# hhv-dcdarknet-varient-3.net
KiCad netlist of a schematic drawn in EAGLE
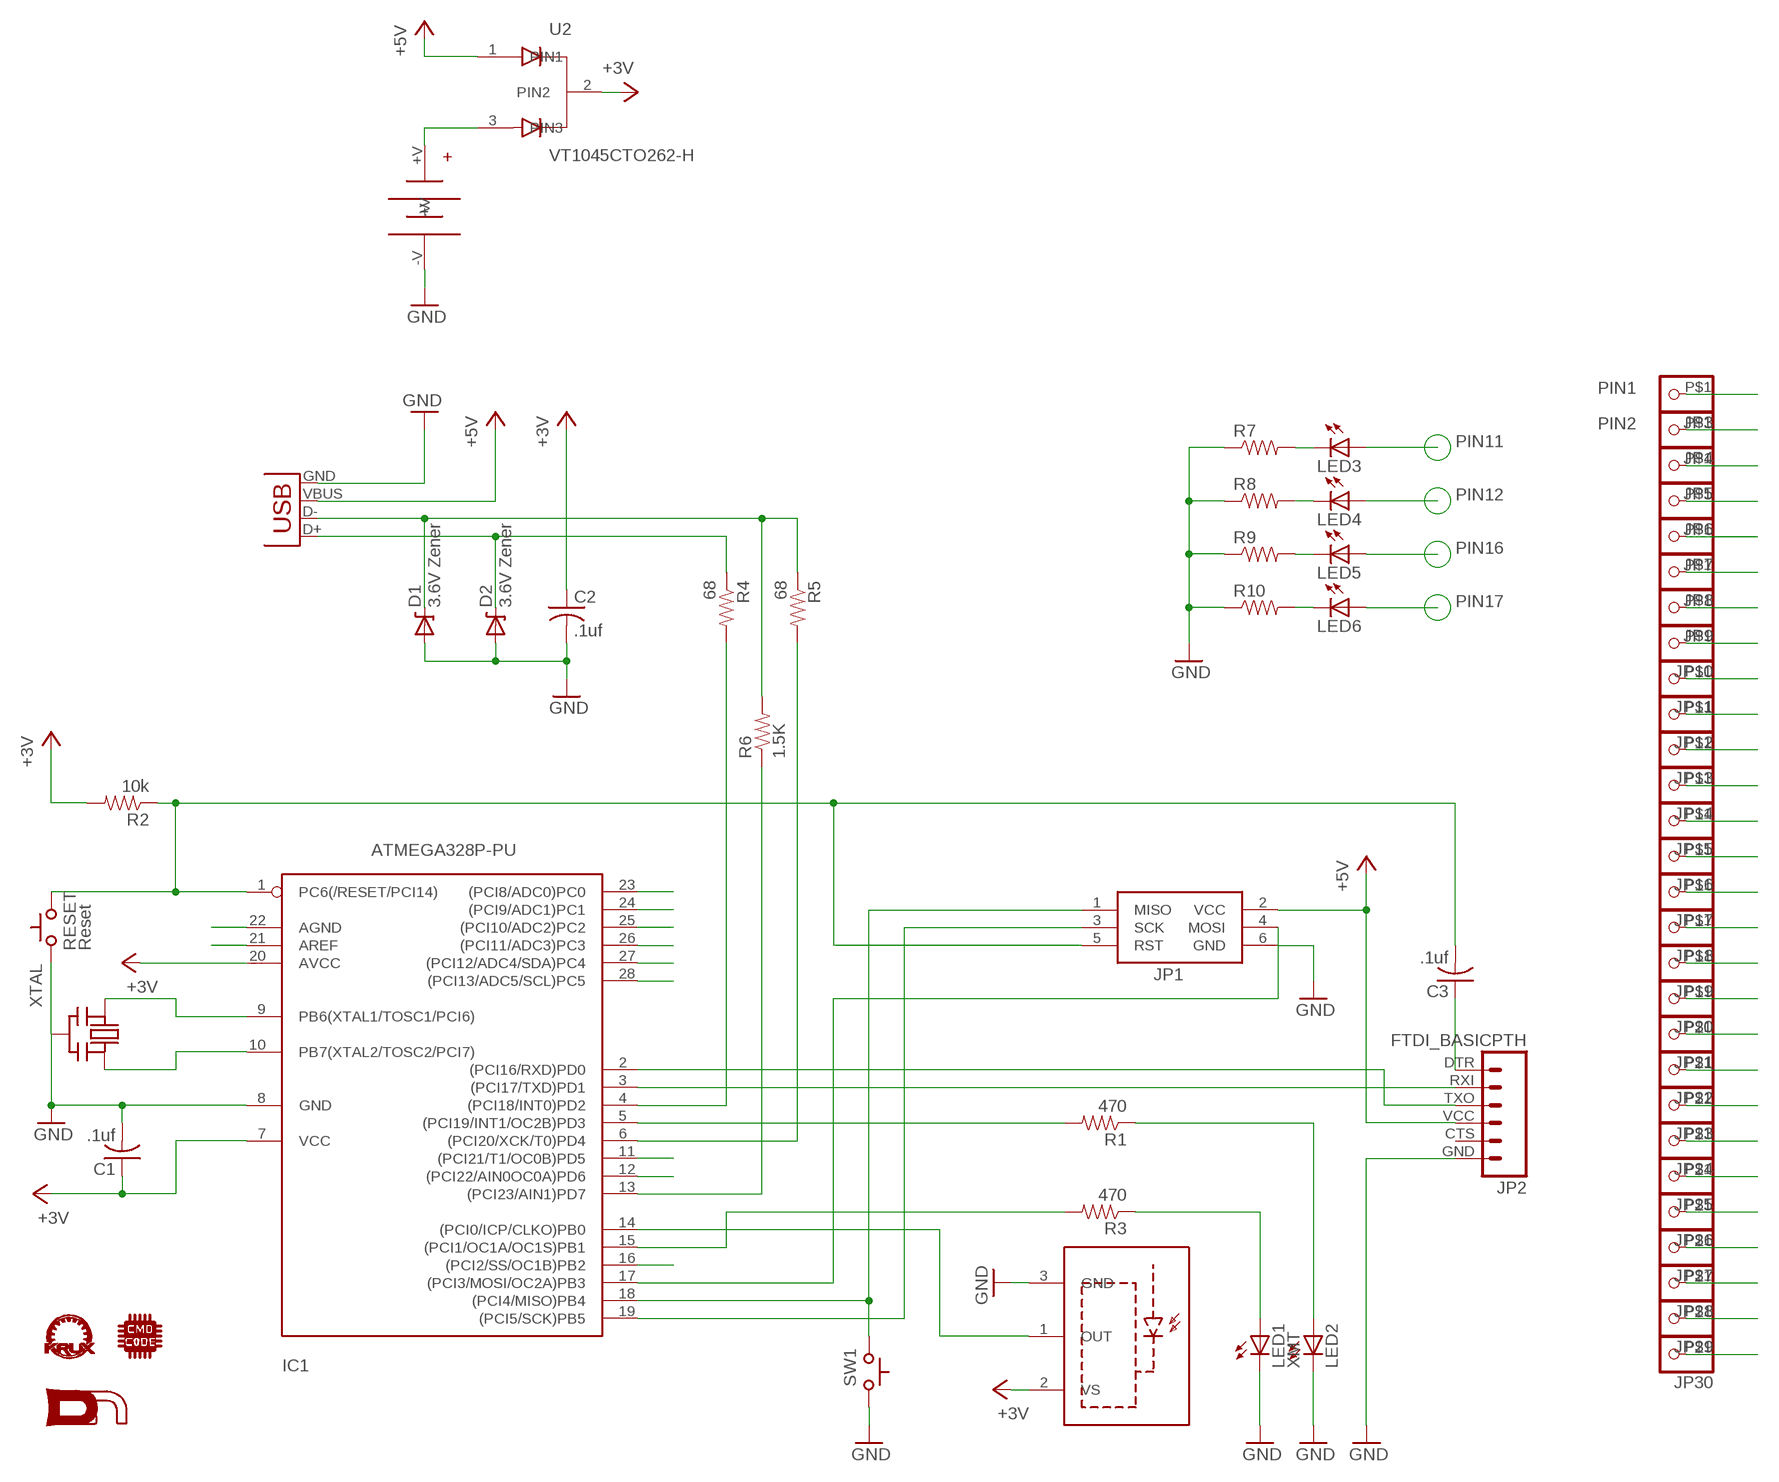
[diagram p0: schematic, sheet 1]

(export (version "E")
  (design (tool "Eeschema 10.0.6"))
  (components
    (comp (ref "C1")
      (value ".1uf")
      (footprint "eagle-import:C025-030X050")
      (libsource (lib "eagle-import") (part "C-US025-030X050"))
    )
    (comp (ref "C2")
      (value ".1uf")
      (footprint "eagle-import:C025-030X050")
      (libsource (lib "eagle-import") (part "C-US025-030X050"))
    )
    (comp (ref "C3")
      (value ".1uf")
      (footprint "eagle-import:C025-030X050")
      (libsource (lib "eagle-import") (part "C-US025-030X050"))
    )
    (comp (ref "D1")
      (value "3.6V Zener")
      (footprint "eagle-import:DIODE-ZENER")
      (libsource (lib "eagle-import") (part "DIODE-ZENERPTH"))
    )
    (comp (ref "D2")
      (value "3.6V Zener")
      (footprint "eagle-import:DIODE-ZENER")
      (libsource (lib "eagle-import") (part "DIODE-ZENERPTH"))
    )
    (comp (ref "IC1")
      (value "ATMEGA328P-PU")
      (footprint "eagle-import:DIL28-3")
      (libsource (lib "eagle-import") (part "ATMEGA168PV-10"))
    )
    (comp (ref "JP1")
      (value "JP1")
      (footprint "eagle-import:AVRISP")
      (libsource (lib "eagle-import") (part "AVRISP-6"))
    )
    (comp (ref "JP2")
      (value "FTDI_BASICPTH")
      (footprint "eagle-import:FTDI_BASIC")
      (libsource (lib "eagle-import") (part "FTDI_BASICPTH"))
    )
    (comp (ref "JP3")
      (value "PINHD-1X11X1_SQUARE")
      (footprint "eagle-import:1X1-SMALL_CUT")
      (libsource (lib "eagle-import") (part "PINHD-1X11X1_SQUARE"))
    )
    (comp (ref "JP4")
      (value "PINHD-1X11X1_SQUARE")
      (footprint "eagle-import:1X1-SMALL_CUT")
      (libsource (lib "eagle-import") (part "PINHD-1X11X1_SQUARE"))
    )
    (comp (ref "JP5")
      (value "PINHD-1X11X1_SQUARE")
      (footprint "eagle-import:1X1-SMALL_CUT")
      (libsource (lib "eagle-import") (part "PINHD-1X11X1_SQUARE"))
    )
    (comp (ref "JP6")
      (value "PINHD-1X11X1_SQUARE")
      (footprint "eagle-import:1X1-SMALL_CUT")
      (libsource (lib "eagle-import") (part "PINHD-1X11X1_SQUARE"))
    )
    (comp (ref "JP7")
      (value "PINHD-1X11X1_SQUARE")
      (footprint "eagle-import:1X1-SMALL_CUT")
      (libsource (lib "eagle-import") (part "PINHD-1X11X1_SQUARE"))
    )
    (comp (ref "JP8")
      (value "PINHD-1X11X1_SQUARE")
      (footprint "eagle-import:1X1-SMALL_CUT")
      (libsource (lib "eagle-import") (part "PINHD-1X11X1_SQUARE"))
    )
    (comp (ref "JP9")
      (value "PINHD-1X11X1_SQUARE")
      (footprint "eagle-import:1X1-SMALL_CUT")
      (libsource (lib "eagle-import") (part "PINHD-1X11X1_SQUARE"))
    )
    (comp (ref "JP10")
      (value "PINHD-1X11X1_SQUARE")
      (footprint "eagle-import:1X1-SMALL_CUT")
      (libsource (lib "eagle-import") (part "PINHD-1X11X1_SQUARE"))
    )
    (comp (ref "JP11")
      (value "PINHD-1X11X1_SQUARE")
      (footprint "eagle-import:1X1-SMALL_CUT")
      (libsource (lib "eagle-import") (part "PINHD-1X11X1_SQUARE"))
    )
    (comp (ref "JP12")
      (value "PINHD-1X11X1_SQUARE")
      (footprint "eagle-import:1X1-SMALL_CUT")
      (libsource (lib "eagle-import") (part "PINHD-1X11X1_SQUARE"))
    )
    (comp (ref "JP13")
      (value "PINHD-1X11X1_SQUARE")
      (footprint "eagle-import:1X1-SMALL_CUT")
      (libsource (lib "eagle-import") (part "PINHD-1X11X1_SQUARE"))
    )
    (comp (ref "JP14")
      (value "PINHD-1X11X1_SQUARE")
      (footprint "eagle-import:1X1-SMALL_CUT")
      (libsource (lib "eagle-import") (part "PINHD-1X11X1_SQUARE"))
    )
    (comp (ref "JP15")
      (value "PINHD-1X11X1_SQUARE")
      (footprint "eagle-import:1X1-SMALL_CUT")
      (libsource (lib "eagle-import") (part "PINHD-1X11X1_SQUARE"))
    )
    (comp (ref "JP16")
      (value "PINHD-1X11X1_SQUARE")
      (footprint "eagle-import:1X1-SMALL_CUT")
      (libsource (lib "eagle-import") (part "PINHD-1X11X1_SQUARE"))
    )
    (comp (ref "JP17")
      (value "PINHD-1X11X1_SQUARE")
      (footprint "eagle-import:1X1-SMALL_CUT")
      (libsource (lib "eagle-import") (part "PINHD-1X11X1_SQUARE"))
    )
    (comp (ref "JP18")
      (value "PINHD-1X11X1_SQUARE")
      (footprint "eagle-import:1X1-SMALL_CUT")
      (libsource (lib "eagle-import") (part "PINHD-1X11X1_SQUARE"))
    )
    (comp (ref "JP19")
      (value "PINHD-1X11X1_SQUARE")
      (footprint "eagle-import:1X1-SMALL_CUT")
      (libsource (lib "eagle-import") (part "PINHD-1X11X1_SQUARE"))
    )
    (comp (ref "JP20")
      (value "PINHD-1X11X1_SQUARE")
      (footprint "eagle-import:1X1-SMALL_CUT")
      (libsource (lib "eagle-import") (part "PINHD-1X11X1_SQUARE"))
    )
    (comp (ref "JP21")
      (value "PINHD-1X11X1_SQUARE")
      (footprint "eagle-import:1X1-SMALL_CUT")
      (libsource (lib "eagle-import") (part "PINHD-1X11X1_SQUARE"))
    )
    (comp (ref "JP22")
      (value "PINHD-1X11X1_SQUARE")
      (footprint "eagle-import:1X1-SMALL_CUT")
      (libsource (lib "eagle-import") (part "PINHD-1X11X1_SQUARE"))
    )
    (comp (ref "JP23")
      (value "PINHD-1X11X1_SQUARE")
      (footprint "eagle-import:1X1-SMALL_CUT")
      (libsource (lib "eagle-import") (part "PINHD-1X11X1_SQUARE"))
    )
    (comp (ref "JP24")
      (value "PINHD-1X11X1_SQUARE")
      (footprint "eagle-import:1X1-SMALL_CUT")
      (libsource (lib "eagle-import") (part "PINHD-1X11X1_SQUARE"))
    )
    (comp (ref "JP25")
      (value "PINHD-1X11X1_SQUARE")
      (footprint "eagle-import:1X1-SMALL_CUT")
      (libsource (lib "eagle-import") (part "PINHD-1X11X1_SQUARE"))
    )
    (comp (ref "JP26")
      (value "PINHD-1X11X1_SQUARE")
      (footprint "eagle-import:1X1-SMALL_CUT")
      (libsource (lib "eagle-import") (part "PINHD-1X11X1_SQUARE"))
    )
    (comp (ref "JP27")
      (value "PINHD-1X11X1_SQUARE")
      (footprint "eagle-import:1X1-SMALL_CUT")
      (libsource (lib "eagle-import") (part "PINHD-1X11X1_SQUARE"))
    )
    (comp (ref "JP28")
      (value "PINHD-1X11X1-SMALL")
      (footprint "eagle-import:1X1-SMALL")
      (libsource (lib "eagle-import") (part "PINHD-1X11X1-SMALL"))
    )
    (comp (ref "JP29")
      (value "PINHD-1X11X1-SMALL")
      (footprint "eagle-import:1X1-SMALL")
      (libsource (lib "eagle-import") (part "PINHD-1X11X1-SMALL"))
    )
    (comp (ref "JP30")
      (value "PINHD-1X11X1-SMALL")
      (footprint "eagle-import:1X1-SMALL")
      (libsource (lib "eagle-import") (part "PINHD-1X11X1-SMALL"))
    )
    (comp (ref "LED1")
      (value "XMT")
      (footprint "eagle-import:LED5MM-FLAT")
      (libsource (lib "eagle-import") (part "LED5MM-FLAT"))
    )
    (comp (ref "LED2")
      (value "LED5MM-FLAT")
      (footprint "eagle-import:LED5MM-FLAT")
      (libsource (lib "eagle-import") (part "LED5MM-FLAT"))
    )
    (comp (ref "LED3")
      (value "LED1206")
      (footprint "eagle-import:LED-1206")
      (libsource (lib "eagle-import") (part "SparkFun_LED1206"))
    )
    (comp (ref "LED4")
      (value "LED1206")
      (footprint "eagle-import:LED-1206")
      (libsource (lib "eagle-import") (part "SparkFun_LED1206"))
    )
    (comp (ref "LED5")
      (value "LED1206")
      (footprint "eagle-import:LED-1206")
      (libsource (lib "eagle-import") (part "SparkFun_LED1206"))
    )
    (comp (ref "LED6")
      (value "LED1206")
      (footprint "eagle-import:LED-1206")
      (libsource (lib "eagle-import") (part "SparkFun_LED1206"))
    )
    (comp (ref "R1")
      (value "470")
      (footprint "eagle-import:AXIAL-0.3")
      (libsource (lib "eagle-import") (part "RESISTORAXIAL-0.3"))
    )
    (comp (ref "R2")
      (value "10k")
      (footprint "eagle-import:AXIAL-0.3")
      (libsource (lib "eagle-import") (part "RESISTORAXIAL-0.3"))
    )
    (comp (ref "R3")
      (value "470")
      (footprint "eagle-import:AXIAL-0.3")
      (libsource (lib "eagle-import") (part "RESISTORAXIAL-0.3"))
    )
    (comp (ref "R4")
      (value "68")
      (footprint "eagle-import:AXIAL-0.3")
      (libsource (lib "eagle-import") (part "RESISTORAXIAL-0.3"))
    )
    (comp (ref "R5")
      (value "68")
      (footprint "eagle-import:AXIAL-0.3")
      (libsource (lib "eagle-import") (part "RESISTORAXIAL-0.3"))
    )
    (comp (ref "R6")
      (value "1.5K")
      (footprint "eagle-import:AXIAL-0.3")
      (libsource (lib "eagle-import") (part "RESISTORAXIAL-0.3"))
    )
    (comp (ref "R7")
      (value "RESISTOR1206")
      (footprint "eagle-import:1206")
      (libsource (lib "eagle-import") (part "SparkFun_RESISTOR1206"))
    )
    (comp (ref "R8")
      (value "RESISTOR1206")
      (footprint "eagle-import:1206")
      (libsource (lib "eagle-import") (part "SparkFun_RESISTOR1206"))
    )
    (comp (ref "R9")
      (value "RESISTOR1206")
      (footprint "eagle-import:1206")
      (libsource (lib "eagle-import") (part "SparkFun_RESISTOR1206"))
    )
    (comp (ref "R10")
      (value "RESISTOR1206")
      (footprint "eagle-import:1206")
      (libsource (lib "eagle-import") (part "SparkFun_RESISTOR1206"))
    )
    (comp (ref "RESET")
      (value "Reset")
      (footprint "eagle-import:TACTILE-2PIN")
      (libsource (lib "eagle-import") (part "SWITCH_TACTILETACTILE-2PIN"))
    )
    (comp (ref "SW1")
      (value "SWITCH_TACTILETACTILE-2PIN")
      (footprint "eagle-import:TACTILE-2PIN")
      (libsource (lib "eagle-import") (part "SWITCH_TACTILETACTILE-2PIN"))
    )
    (comp (ref "U$1")
      (value "DN_LOGO")
      (footprint "eagle-import:DN_LOGO")
      (libsource (lib "eagle-import") (part "DN_LOGO"))
    )
    (comp (ref "U$2")
      (value "CMDC0DE_LOGO")
      (footprint "eagle-import:CMDC0DE")
      (libsource (lib "eagle-import") (part "CMDC0DE_LOGO"))
    )
    (comp (ref "U$3")
      (value "KRUX_LOGO")
      (footprint "eagle-import:KRUX_LOGO")
      (libsource (lib "eagle-import") (part "KRUX_LOGO"))
    )
    (comp (ref "U$5")
      (value "12BH423-GR3-CELL_NOBORDER")
      (footprint "eagle-import:3-AAA-CELL_NOBORDER")
      (libsource (lib "eagle-import") (part "12BH423-GR3-CELL_NOBORDER"))
    )
    (comp (ref "U1")
      (value "RCV")
      (footprint "eagle-import:IR-MODULE")
      (libsource (lib "eagle-import") (part "SOP22"))
    )
    (comp (ref "U2")
      (value "VT1045CTO262-H")
      (footprint "eagle-import:TO262-H")
      (libsource (lib "eagle-import") (part "VT1045CTO262-H"))
    )
    (comp (ref "X2")
      (value "USB")
      (footprint "eagle-import:USB-B-PTH")
      (libsource (lib "eagle-import") (part "USBPTH"))
    )
    (comp (ref "XTAL")
      (value "CERMOSCILL-THM")
      (footprint "eagle-import:CERM_OSC")
      (libsource (lib "eagle-import") (part "CERMOSCILL-THM"))
    )
  )
  (nets
    (net (code "1") (name "+3V") (class "Default")
      (node (ref "C1") (pin "1") (pinfunction "1_1") (pintype "passive"))
      (node (ref "C2") (pin "1") (pinfunction "1_1") (pintype "passive"))
      (node (ref "IC1") (pin "20") (pinfunction "AVCC_20") (pintype "bidirectional"))
      (node (ref "IC1") (pin "7") (pinfunction "VCC_7") (pintype "bidirectional"))
      (node (ref "JP22") (pin "P$1") (pinfunction "1_P$1") (pintype "passive"))
      (node (ref "JP9") (pin "P$1") (pinfunction "1_P$1") (pintype "passive"))
      (node (ref "R2") (pin "P$2") (pinfunction "2_P$2") (pintype "passive"))
      (node (ref "U1") (pin "2") (pinfunction "VS_2") (pintype "bidirectional"))
      (node (ref "U2") (pin "2") (pinfunction "PIN2_2") (pintype "bidirectional"))
    )
    (net (code "2") (name "+5V") (class "Default")
      (node (ref "JP1") (pin "2") (pinfunction "VCC_2") (pintype "power_in"))
      (node (ref "JP2") (pin "VCC") (pinfunction "4_VCC") (pintype "passive"))
      (node (ref "U2") (pin "1") (pinfunction "PIN1_1") (pintype "bidirectional"))
      (node (ref "X2") (pin "VBUS") (pinfunction "VBUS_VBUS") (pintype "bidirectional"))
    )
    (net (code "3") (name "/PIN1") (class "Default")
      (node (ref "C3") (pin "2") (pinfunction "2_2") (pintype "passive"))
      (node (ref "IC1") (pin "1") (pinfunction "PC6(/RESET/PCI14)_1") (pintype "bidirectional"))
      (node (ref "JP1") (pin "5") (pinfunction "RST_5") (pintype "output"))
      (node (ref "JP3") (pin "P$1") (pinfunction "1_P$1") (pintype "passive"))
      (node (ref "R2") (pin "P$1") (pinfunction "1_P$1") (pintype "passive"))
      (node (ref "RESET") (pin "P$1") (pinfunction "A_P$1") (pintype "passive"))
    )
    (net (code "4") (name "/PIN2") (class "Default")
      (node (ref "IC1") (pin "2") (pinfunction "(PCI16/RXD)PD0_2") (pintype "bidirectional"))
      (node (ref "JP2") (pin "TXO") (pinfunction "3_TXO") (pintype "passive"))
      (node (ref "JP4") (pin "P$1") (pinfunction "1_P$1") (pintype "passive"))
    )
    (net (code "5") (name "/PIN3") (class "Default")
      (node (ref "IC1") (pin "3") (pinfunction "(PCI17/TXD)PD1_3") (pintype "bidirectional"))
      (node (ref "JP2") (pin "RXI") (pinfunction "2_RXI") (pintype "passive"))
      (node (ref "JP5") (pin "P$1") (pinfunction "1_P$1") (pintype "passive"))
    )
    (net (code "6") (name "/PIN4") (class "Default")
      (node (ref "IC1") (pin "4") (pinfunction "(PCI18/INT0)PD2_4") (pintype "bidirectional"))
      (node (ref "JP6") (pin "P$1") (pinfunction "1_P$1") (pintype "passive"))
      (node (ref "R4") (pin "P$2") (pinfunction "2_P$2") (pintype "passive"))
    )
    (net (code "7") (name "/PIN5") (class "Default")
      (node (ref "IC1") (pin "5") (pinfunction "(PCI19/INT1/OC2B)PD3_5") (pintype "bidirectional"))
      (node (ref "JP7") (pin "P$1") (pinfunction "1_P$1") (pintype "passive"))
      (node (ref "R1") (pin "P$2") (pinfunction "2_P$2") (pintype "passive"))
    )
    (net (code "8") (name "/PIN6") (class "Default")
      (node (ref "IC1") (pin "6") (pinfunction "(PCI20/XCK/T0)PD4_6") (pintype "bidirectional"))
      (node (ref "JP8") (pin "P$1") (pinfunction "1_P$1") (pintype "passive"))
      (node (ref "R5") (pin "P$2") (pinfunction "2_P$2") (pintype "passive"))
    )
    (net (code "9") (name "/PIN9") (class "Default")
      (node (ref "IC1") (pin "9") (pinfunction "PB6(XTAL1/TOSC1/PCI6)_9") (pintype "bidirectional"))
      (node (ref "JP11") (pin "P$1") (pinfunction "1_P$1") (pintype "passive"))
      (node (ref "XTAL") (pin "P$1") (pinfunction "IN_P$1") (pintype "bidirectional"))
    )
    (net (code "10") (name "/PIN10") (class "Default")
      (node (ref "IC1") (pin "10") (pinfunction "PB7(XTAL2/TOSC2/PCI7)_10") (pintype "bidirectional"))
      (node (ref "JP12") (pin "P$1") (pinfunction "1_P$1") (pintype "passive"))
      (node (ref "XTAL") (pin "P$3") (pinfunction "OUT_P$3") (pintype "bidirectional"))
    )
    (net (code "11") (name "/PIN11") (class "Default")
      (node (ref "IC1") (pin "11") (pinfunction "(PCI21/T1/OC0B)PD5_11") (pintype "bidirectional"))
      (node (ref "JP13") (pin "P$1") (pinfunction "1_P$1") (pintype "passive"))
      (node (ref "LED3") (pin "A") (pinfunction "A_A") (pintype "passive"))
    )
    (net (code "12") (name "/PIN12") (class "Default")
      (node (ref "IC1") (pin "12") (pinfunction "(PCI22/AIN0OC0A)PD6_12") (pintype "bidirectional"))
      (node (ref "JP14") (pin "P$1") (pinfunction "1_P$1") (pintype "passive"))
      (node (ref "LED4") (pin "A") (pinfunction "A_A") (pintype "passive"))
    )
    (net (code "13") (name "/PIN13") (class "Default")
      (node (ref "IC1") (pin "13") (pinfunction "(PCI23/AIN1)PD7_13") (pintype "bidirectional"))
      (node (ref "JP15") (pin "P$1") (pinfunction "1_P$1") (pintype "passive"))
      (node (ref "R6") (pin "P$1") (pinfunction "1_P$1") (pintype "passive"))
    )
    (net (code "14") (name "/PIN14") (class "Default")
      (node (ref "IC1") (pin "14") (pinfunction "(PCI0/ICP/CLKO)PB0_14") (pintype "bidirectional"))
      (node (ref "JP16") (pin "P$1") (pinfunction "1_P$1") (pintype "passive"))
      (node (ref "U1") (pin "1") (pinfunction "OUT_1") (pintype "bidirectional"))
    )
    (net (code "15") (name "/PIN15") (class "Default")
      (node (ref "IC1") (pin "15") (pinfunction "(PCI1/OC1A/OC1S)PB1_15") (pintype "bidirectional"))
      (node (ref "JP17") (pin "P$1") (pinfunction "1_P$1") (pintype "passive"))
      (node (ref "R3") (pin "P$2") (pinfunction "2_P$2") (pintype "passive"))
    )
    (net (code "16") (name "/PIN16") (class "Default")
      (node (ref "IC1") (pin "16") (pinfunction "(PCI2/SS/OC1B)PB2_16") (pintype "bidirectional"))
      (node (ref "JP18") (pin "P$1") (pinfunction "1_P$1") (pintype "passive"))
      (node (ref "LED5") (pin "A") (pinfunction "A_A") (pintype "passive"))
    )
    (net (code "17") (name "/PIN17") (class "Default")
      (node (ref "IC1") (pin "17") (pinfunction "(PCI3/MOSI/OC2A)PB3_17") (pintype "bidirectional"))
      (node (ref "JP1") (pin "4") (pinfunction "MOSI_4") (pintype "output"))
      (node (ref "JP19") (pin "P$1") (pinfunction "1_P$1") (pintype "passive"))
      (node (ref "LED6") (pin "A") (pinfunction "A_A") (pintype "passive"))
    )
    (net (code "18") (name "/PIN18") (class "Default")
      (node (ref "IC1") (pin "18") (pinfunction "(PCI4/MISO)PB4_18") (pintype "bidirectional"))
      (node (ref "JP1") (pin "1") (pinfunction "MISO_1") (pintype "input"))
      (node (ref "JP20") (pin "P$1") (pinfunction "1_P$1") (pintype "passive"))
      (node (ref "SW1") (pin "P$2") (pinfunction "C_P$2") (pintype "passive"))
    )
    (net (code "19") (name "/PIN19") (class "Default")
      (node (ref "IC1") (pin "19") (pinfunction "(PCI5/SCK)PB5_19") (pintype "bidirectional"))
      (node (ref "JP1") (pin "3") (pinfunction "SCK_3") (pintype "output"))
      (node (ref "JP21") (pin "P$1") (pinfunction "1_P$1") (pintype "passive"))
    )
    (net (code "20") (name "/PIN21") (class "Default")
      (node (ref "IC1") (pin "21") (pinfunction "AREF_21") (pintype "bidirectional"))
      (node (ref "JP23") (pin "P$1") (pinfunction "1_P$1") (pintype "passive"))
    )
    (net (code "21") (name "/PIN22") (class "Default")
      (node (ref "IC1") (pin "22") (pinfunction "AGND_22") (pintype "bidirectional"))
      (node (ref "JP24") (pin "P$1") (pinfunction "1_P$1") (pintype "passive"))
    )
    (net (code "22") (name "/PIN23") (class "Default")
      (node (ref "IC1") (pin "23") (pinfunction "(PCI8/ADC0)PC0_23") (pintype "bidirectional"))
      (node (ref "JP25") (pin "P$1") (pinfunction "1_P$1") (pintype "passive"))
    )
    (net (code "23") (name "/PIN24") (class "Default")
      (node (ref "IC1") (pin "24") (pinfunction "(PCI9/ADC1)PC1_24") (pintype "bidirectional"))
      (node (ref "JP26") (pin "P$1") (pinfunction "1_P$1") (pintype "passive"))
    )
    (net (code "24") (name "/PIN25") (class "Default")
      (node (ref "IC1") (pin "25") (pinfunction "(PCI10/ADC2)PC2_25") (pintype "bidirectional"))
      (node (ref "JP27") (pin "P$1") (pinfunction "1_P$1") (pintype "passive"))
    )
    (net (code "25") (name "/PIN26") (class "Default")
      (node (ref "IC1") (pin "26") (pinfunction "(PCI11/ADC3)PC3_26") (pintype "bidirectional"))
      (node (ref "JP28") (pin "P$1") (pinfunction "1_P$1") (pintype "passive"))
    )
    (net (code "26") (name "/PIN27") (class "Default")
      (node (ref "IC1") (pin "27") (pinfunction "(PCI12/ADC4/SDA)PC4_27") (pintype "bidirectional"))
      (node (ref "JP29") (pin "P$1") (pinfunction "1_P$1") (pintype "passive"))
    )
    (net (code "27") (name "/PIN28") (class "Default")
      (node (ref "IC1") (pin "28") (pinfunction "(PCI13/ADC5/SCL)PC5_28") (pintype "bidirectional"))
      (node (ref "JP30") (pin "P$1") (pinfunction "1_P$1") (pintype "passive"))
    )
    (net (code "28") (name "GND") (class "Default")
      (node (ref "C1") (pin "2") (pinfunction "2_2") (pintype "passive"))
      (node (ref "C2") (pin "2") (pinfunction "2_2") (pintype "passive"))
      (node (ref "D1") (pin "P$2") (pinfunction "A_P$2") (pintype "passive"))
      (node (ref "D2") (pin "P$2") (pinfunction "A_P$2") (pintype "passive"))
      (node (ref "IC1") (pin "8") (pinfunction "GND_8") (pintype "bidirectional"))
      (node (ref "JP1") (pin "6") (pinfunction "GND_6") (pintype "power_in"))
      (node (ref "JP10") (pin "P$1") (pinfunction "1_P$1") (pintype "passive"))
      (node (ref "JP2") (pin "GND") (pinfunction "6_GND") (pintype "passive"))
      (node (ref "LED1") (pin "K") (pinfunction "C_K") (pintype "passive"))
      (node (ref "LED2") (pin "K") (pinfunction "C_K") (pintype "passive"))
      (node (ref "R10") (pin "1") (pinfunction "1_1") (pintype "passive"))
      (node (ref "R7") (pin "1") (pinfunction "1_1") (pintype "passive"))
      (node (ref "R8") (pin "1") (pinfunction "1_1") (pintype "passive"))
      (node (ref "R9") (pin "1") (pinfunction "1_1") (pintype "passive"))
      (node (ref "RESET") (pin "P$2") (pinfunction "C_P$2") (pintype "passive"))
      (node (ref "SW1") (pin "P$1") (pinfunction "A_P$1") (pintype "passive"))
      (node (ref "U$5") (pin "-V") (pinfunction "-V_-V") (pintype "bidirectional"))
      (node (ref "U1") (pin "3") (pinfunction "GND_3") (pintype "bidirectional"))
      (node (ref "X2") (pin "GND") (pinfunction "GND_GND") (pintype "bidirectional"))
      (node (ref "XTAL") (pin "P$2") (pinfunction "GND_P$2") (pintype "bidirectional"))
    )
    (net (code "29") (name "Net-(D1-C)") (class "Default")
      (node (ref "D1") (pin "P$1") (pinfunction "C_P$1") (pintype "passive"))
      (node (ref "R5") (pin "P$1") (pinfunction "1_P$1") (pintype "passive"))
      (node (ref "R6") (pin "P$2") (pinfunction "2_P$2") (pintype "passive"))
      (node (ref "X2") (pin "D-") (pinfunction "D-_D-") (pintype "bidirectional"))
    )
    (net (code "30") (name "Net-(D2-C)") (class "Default")
      (node (ref "D2") (pin "P$1") (pinfunction "C_P$1") (pintype "passive"))
      (node (ref "R4") (pin "P$1") (pinfunction "1_P$1") (pintype "passive"))
      (node (ref "X2") (pin "D+") (pinfunction "D+_D+") (pintype "bidirectional"))
    )
    (net (code "31") (name "Net-(JP2-1)") (class "Default")
      (node (ref "C3") (pin "1") (pinfunction "1_1") (pintype "passive"))
      (node (ref "JP2") (pin "DTR") (pinfunction "1_DTR") (pintype "passive"))
    )
    (net (code "32") (name "Net-(LED3-PadC)") (class "Default")
      (node (ref "LED3") (pin "C") (pinfunction "C_C") (pintype "passive"))
      (node (ref "R7") (pin "2") (pinfunction "2_2") (pintype "passive"))
    )
    (net (code "33") (name "Net-(LED4-PadC)") (class "Default")
      (node (ref "LED4") (pin "C") (pinfunction "C_C") (pintype "passive"))
      (node (ref "R8") (pin "2") (pinfunction "2_2") (pintype "passive"))
    )
    (net (code "34") (name "Net-(LED5-PadC)") (class "Default")
      (node (ref "LED5") (pin "C") (pinfunction "C_C") (pintype "passive"))
      (node (ref "R9") (pin "2") (pinfunction "2_2") (pintype "passive"))
    )
    (net (code "35") (name "Net-(LED6-PadC)") (class "Default")
      (node (ref "LED6") (pin "C") (pinfunction "C_C") (pintype "passive"))
      (node (ref "R10") (pin "2") (pinfunction "2_2") (pintype "passive"))
    )
    (net (code "36") (name "Net-(R1-1)") (class "Default")
      (node (ref "LED2") (pin "A") (pinfunction "A_A") (pintype "passive"))
      (node (ref "R1") (pin "P$1") (pinfunction "1_P$1") (pintype "passive"))
    )
    (net (code "37") (name "Net-(R3-1)") (class "Default")
      (node (ref "LED1") (pin "A") (pinfunction "A_A") (pintype "passive"))
      (node (ref "R3") (pin "P$1") (pinfunction "1_P$1") (pintype "passive"))
    )
    (net (code "38") (name "Net-(U2-PIN3)") (class "Default")
      (node (ref "U$5") (pin "+V") (pinfunction "+V_+V") (pintype "bidirectional"))
      (node (ref "U2") (pin "3") (pinfunction "PIN3_3") (pintype "bidirectional"))
    )
    (net (code "39") (name "unconnected-(JP2-5-PadCTS)") (class "Default")
      (node (ref "JP2") (pin "CTS") (pinfunction "5_CTS") (pintype "passive"))
    )
  )
)
